# boost_schematic.net
KiCad netlist of a schematic drawn in Altium Designer
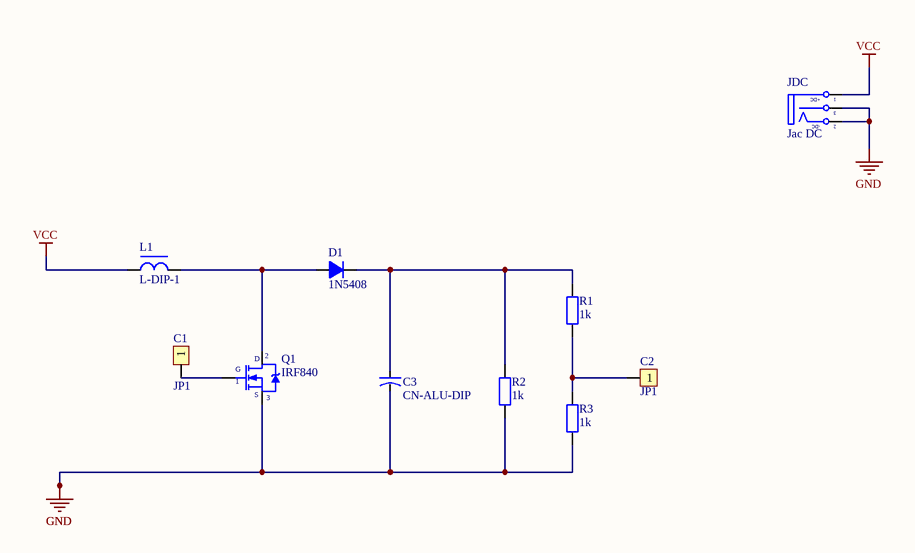
[diagram p0: boost schematic.SchDoc]

(export (version "E")
  (design (tool "Eeschema 10.0.6"))
  (components
    (comp (ref "C1")
      (value "JP1")
      (footprint "JP1-D1T")
      (description "WR-PHD 2.54 mm Angled Socket Header")
      (fields
        (field (name "MANUFACTURER") "Würth Elektronik eiSos GmbH")
        (field (name "PARTNO") "613002143121")
        (field (name "CREATED BY") "Karrer Zheng")
      )
      (libsource (lib "My Library") (part "JP1"))
    )
    (comp (ref "C2")
      (value "JP1")
      (footprint "JP1-D1T")
      (description "WR-PHD 2.54 mm Angled Socket Header")
      (fields
        (field (name "MANUFACTURER") "Würth Elektronik eiSos GmbH")
        (field (name "PARTNO") "613002143121")
        (field (name "CREATED BY") "Karrer Zheng")
      )
      (libsource (lib "") (part "JP1_1"))
    )
    (comp (ref "C3")
      (value "CN-ALU-DIP")
      (footprint "CA-ALU-2.54")
      (description "Capacitor (Semiconductor SIM Model)")
      (fields (field (name "PUBLISHER") "Altium Limited"))
      (libsource (lib "My Library") (part "CN-ALU-DIP"))
    )
    (comp (ref "D1")
      (value "1N5408")
      (footprint "D5A")
      (description "Diode 5A")
      (libsource (lib "My Library") (part "D5A"))
    )
    (comp (ref "JDC")
      (value "Jac DC")
      (footprint "DC-IN")
      (description "Jac DC input")
      (libsource (lib "My Library") (part "DCIN"))
    )
    (comp (ref "L1")
      (value "L-DIP-1")
      (footprint "L-DIP-M-5.3")
      (description "Inductor")
      (libsource (lib "My Library") (part "L-DIP-1"))
    )
    (comp (ref "Q1")
      (value "IRF840")
      (footprint "QTO-220")
      (description "MOSFET N - CHANNEL 500V - 0.75 - 8A - TO-220")
      (libsource (lib "My Library") (part "IRF840"))
    )
    (comp (ref "R1")
      (value "1k")
      (footprint "R1/4W")
      (description "Resistor 1/4W")
      (libsource (lib "My Library") (part "R1/4W"))
    )
    (comp (ref "R2")
      (value "1k")
      (footprint "R1/4W")
      (description "Resistor 1/4W")
      (libsource (lib "My Library") (part "R1/4W"))
    )
    (comp (ref "R3")
      (value "1k")
      (footprint "R1/4W")
      (description "Resistor 1/4W")
      (libsource (lib "My Library") (part "R1/4W"))
    )
  )
  (nets
    (net (code "1") (name "GND") (class "Default")
      (node (ref "C3") (pin "2") (pinfunction "2_2") (pintype "passive"))
      (node (ref "JDC") (pin "2") (pinfunction "TN_2") (pintype "passive"))
      (node (ref "JDC") (pin "3") (pinfunction "S_3") (pintype "power_in"))
      (node (ref "Q1") (pin "3") (pinfunction "S_3") (pintype "passive"))
      (node (ref "R2") (pin "2") (pinfunction "2_2") (pintype "passive"))
      (node (ref "R3") (pin "2") (pinfunction "2_2") (pintype "passive"))
    )
    (net (code "2") (name "Net-(C2-Pad1)") (class "Default")
      (node (ref "C2") (pin "1") (pinfunction "1_1") (pintype "passive"))
      (node (ref "R1") (pin "2") (pinfunction "2_2") (pintype "passive"))
      (node (ref "R3") (pin "1") (pinfunction "1_1") (pintype "passive"))
    )
    (net (code "3") (name "Net-(D1-A)") (class "Default")
      (node (ref "D1") (pin "1") (pinfunction "A_1") (pintype "passive"))
      (node (ref "L1") (pin "2") (pinfunction "2_2") (pintype "passive"))
      (node (ref "Q1") (pin "2") (pinfunction "D_2") (pintype "passive"))
    )
    (net (code "4") (name "Net-(D1-K)") (class "Default")
      (node (ref "C3") (pin "1") (pinfunction "1_1") (pintype "passive"))
      (node (ref "D1") (pin "2") (pinfunction "K_2") (pintype "passive"))
      (node (ref "R1") (pin "1") (pinfunction "1_1") (pintype "passive"))
      (node (ref "R2") (pin "1") (pinfunction "1_1") (pintype "passive"))
    )
    (net (code "5") (name "Net-(Q1-G)") (class "Default")
      (node (ref "C1") (pin "1") (pinfunction "1_1") (pintype "passive"))
      (node (ref "Q1") (pin "1") (pinfunction "G_1") (pintype "passive"))
    )
    (net (code "6") (name "VCC") (class "Default")
      (node (ref "JDC") (pin "1") (pinfunction "T_1") (pintype "passive"))
      (node (ref "L1") (pin "1") (pinfunction "1_1") (pintype "passive"))
    )
  )
)
